# OTimCon_Station.net
KiCad netlist of a schematic drawn in Altium Designer
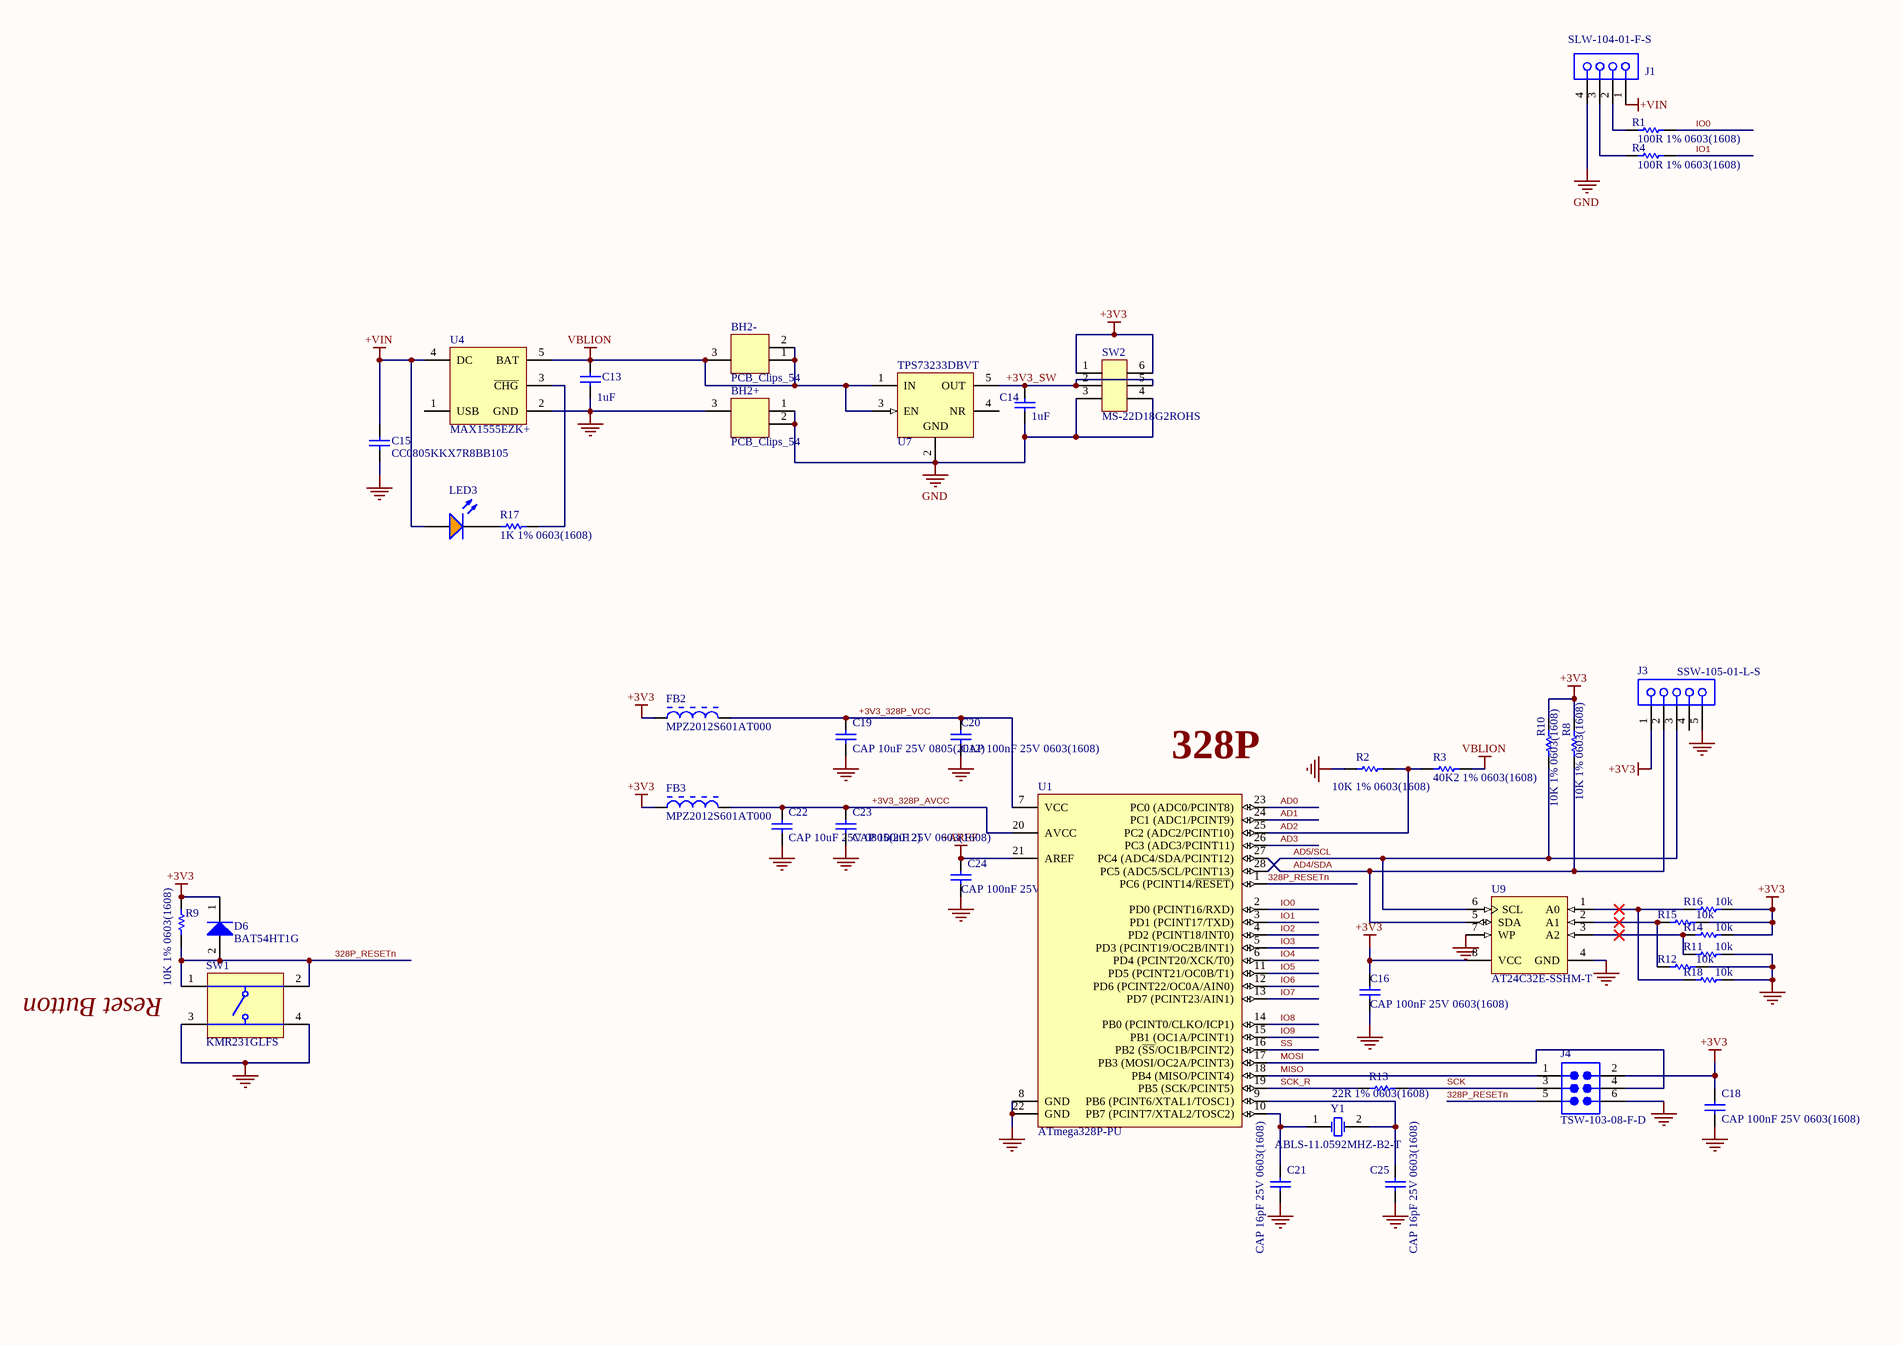
[diagram p0: OTimCon_Station.SchDoc, left]
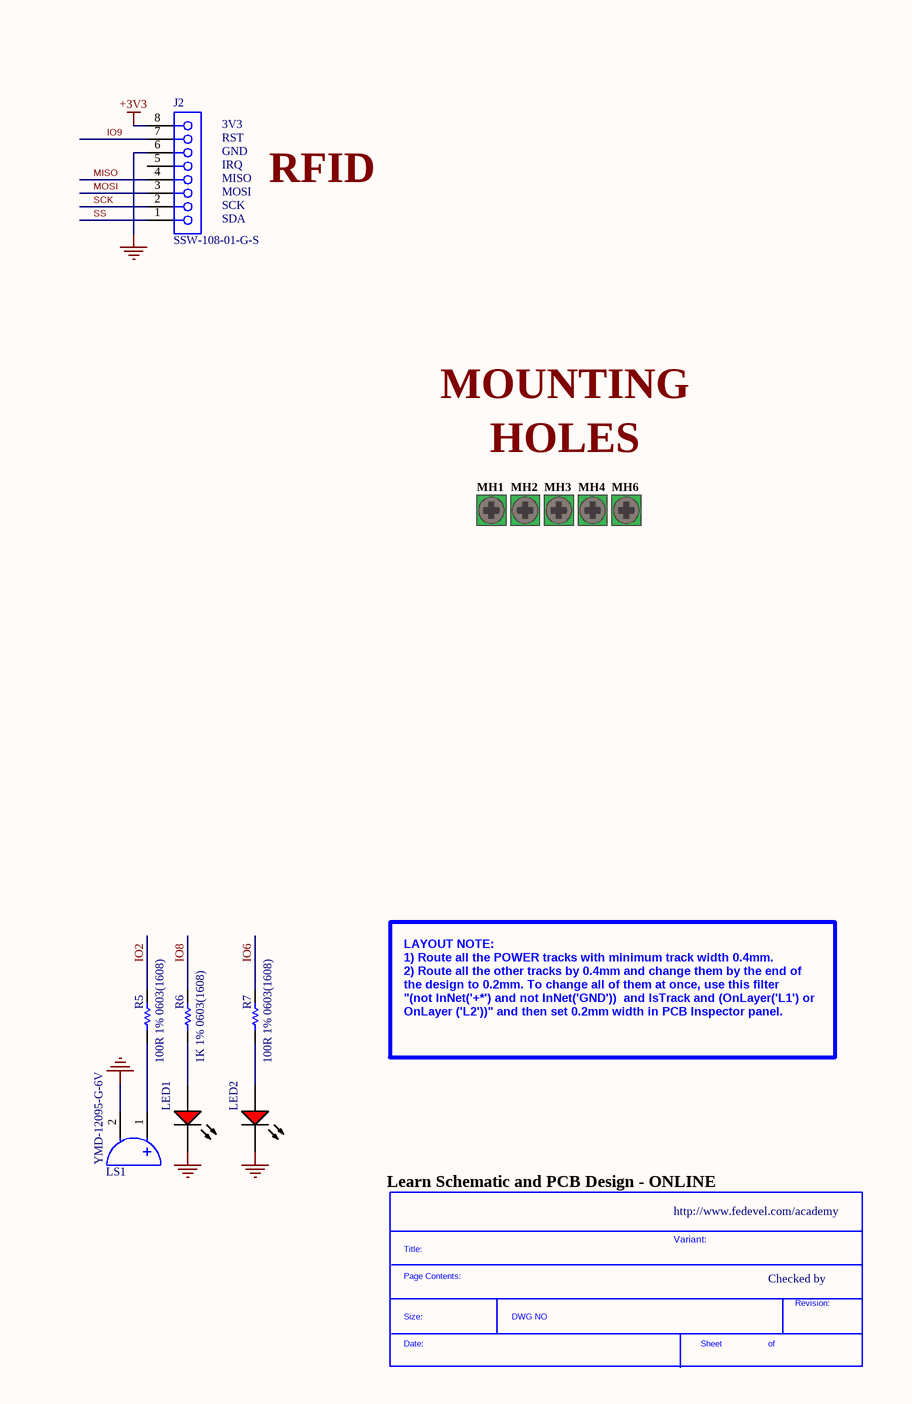
[diagram p1: OTimCon_Station.SchDoc, right]

(export (version "E")
  (design (tool "Eeschema 10.0.6"))
  (components
    (comp (ref "*") (value "SDTitleBlock") (libsource (lib "*") (part "SDTitleBlock")))
    (comp (ref "BH2+")
      (value "PCB_Clips_54")
      (footprint "KEYSTONE-CLIPS_54-3_V")
      (description "PC Battery Clip, Catalog No.54, Spring Steel, Body 18.102 x 13.004 mm, THM")
      (fields (field (name "MANUFACTURER") "Keystone"))
      (libsource (lib "Altium Content Vault") (part "KEYSTONE-CLIPS_54-3"))
    )
    (comp (ref "BH2-")
      (value "PCB_Clips_54")
      (footprint "KEYSTONE-CLIPS_54-3_V")
      (description "PC Battery Clip, Catalog No.54, Spring Steel, Body 18.102 x 13.004 mm, THM")
      (fields (field (name "MANUFACTURER") "Keystone"))
      (libsource (lib "") (part "KEYSTONE-CLIPS_54-3_1"))
    )
    (comp (ref "C13")
      (value "CC0805KKX7R8BB105")
      (footprint "CAPC2013X145X50ML20T25")
      (description "Chip Capacitor, 1 uF, 25 V, 10%, -55 to 125 degC, 0805 (2012 Metric), RoHS, Tape and Reel")
      (fields
        (field (name "CAPACITANCE") "1uF")
        (field (name "MANUFACTURER") "Yageo")
        (field (name "TOLERANCE") "10%")
      )
      (libsource (lib "Altium Content Vault") (part "CAP-NP-2"))
    )
    (comp (ref "C14")
      (value "CC0805KKX7R8BB105")
      (footprint "CAPC2013X145X50ML20T25")
      (description "Chip Capacitor, 1 uF, 25 V, 10%, -55 to 125 degC, 0805 (2012 Metric), RoHS, Tape and Reel")
      (fields
        (field (name "CAPACITANCE") "1uF")
        (field (name "MANUFACTURER") "Yageo")
        (field (name "TOLERANCE") "10%")
      )
      (libsource (lib "Altium Content Vault") (part "CAP-NP-2"))
    )
    (comp (ref "C15")
      (value "CC0805KKX7R8BB105")
      (footprint "CAPC2013X145X50ML20T25")
      (description "Chip Capacitor, 1 uF, 25 V, 10%, -55 to 125 degC, 0805 (2012 Metric), RoHS, Tape and Reel")
      (fields (field (name "MANUFACTURER") "Yageo") (field (name "TOLERANCE") "10%"))
      (libsource (lib "Altium Content Vault") (part "CAP-NP-2"))
    )
    (comp (ref "C16")
      (value "CAP 100nF 25V 0603(1608)")
      (footprint "CAPC0603(1608)100_M")
      (description "CAP 100nF 25V ±10% 0603 (1608 Metric) Thickness 1mm SMD")
      (fields (field (name "TOLERANCE") "Â±10%"))
      (libsource (lib "Altium Content Vault") (part "CAP"))
    )
    (comp (ref "C18")
      (value "CAP 100nF 25V 0603(1608)")
      (footprint "CAPC0603(1608)100_M")
      (description "CAP 100nF 25V ±10% 0603 (1608 Metric) Thickness 1mm SMD")
      (fields (field (name "TOLERANCE") "Â±10%"))
      (libsource (lib "Altium Content Vault") (part "CAP"))
    )
    (comp (ref "C19")
      (value "CAP 10uF 25V 0805(2012)")
      (footprint "CAPC0805(2012)145_N")
      (description "CAP 10uF 25V ±10% 0805 (2012 Metric) Thickness 1.45mm SMD")
      (fields (field (name "TOLERANCE") "Â±10%"))
      (libsource (lib "Altium Content Vault") (part "CAP"))
    )
    (comp (ref "C20")
      (value "CAP 100nF 25V 0603(1608)")
      (footprint "CAPC0603(1608)100_M")
      (description "CAP 100nF 25V ±10% 0603 (1608 Metric) Thickness 1mm SMD")
      (fields (field (name "TOLERANCE") "Â±10%"))
      (libsource (lib "Altium Content Vault") (part "CAP"))
    )
    (comp (ref "C21")
      (value "CAP 16pF 25V 0603(1608)")
      (footprint "CAPC0603(1608)100_L")
      (description "CAP 16pF 25V ±10% 0603 (1608 Metric) Thickness 1mm SMD")
      (fields (field (name "TOLERANCE") "Â±10%"))
      (libsource (lib "Altium Content Vault") (part "CAP"))
    )
    (comp (ref "C22")
      (value "CAP 10uF 25V 0805(2012)")
      (footprint "CAPC0805(2012)145_N")
      (description "CAP 10uF 25V ±10% 0805 (2012 Metric) Thickness 1.45mm SMD")
      (fields (field (name "TOLERANCE") "Â±10%"))
      (libsource (lib "Altium Content Vault") (part "CAP"))
    )
    (comp (ref "C23")
      (value "CAP 100nF 25V 0603(1608)")
      (footprint "CAPC0603(1608)100_M")
      (description "CAP 100nF 25V ±10% 0603 (1608 Metric) Thickness 1mm SMD")
      (fields (field (name "TOLERANCE") "Â±10%"))
      (libsource (lib "Altium Content Vault") (part "CAP"))
    )
    (comp (ref "C24")
      (value "CAP 100nF 25V 0603(1608)")
      (footprint "CAPC0603(1608)100_M")
      (description "CAP 100nF 25V ±10% 0603 (1608 Metric) Thickness 1mm SMD")
      (fields (field (name "TOLERANCE") "Â±10%"))
      (libsource (lib "Altium Content Vault") (part "CAP"))
    )
    (comp (ref "C25")
      (value "CAP 16pF 25V 0603(1608)")
      (footprint "CAPC0603(1608)100_L")
      (description "CAP 16pF 25V ±10% 0603 (1608 Metric) Thickness 1mm SMD")
      (fields (field (name "TOLERANCE") "Â±10%"))
      (libsource (lib "Altium Content Vault") (part "CAP"))
    )
    (comp (ref "D6")
      (value "BAT54HT1G")
      (footprint "ONSC-SOD-323-2-477-02_V")
      (description "Schottky Barrier Diode, 2-Pin SOD-323, Pb-Free, Tape and Reel")
      (fields (field (name "MANUFACTURER") "On Semiconductor"))
      (libsource (lib "Altium Content Vault") (part "ONSC-D-K1A2-2"))
    )
    (comp (ref "FB2")
      (value "MPZ2012S601AT000")
      (footprint "TDK-MPZ2012_V")
      (description "Chip Bead, 0.1 Ohm, 2 A, -55 to 125 degC, 2-Pin SMD (0805), RoHS, Tape and Reel")
      (fields (field (name "PCN PART NUMBER") "MMZ,MPSSeriesOct/2014") (field (name "MANUFACTURER") "TDK"))
      (libsource (lib "Altium Content Vault") (part "BEAD-2"))
    )
    (comp (ref "FB3")
      (value "MPZ2012S601AT000")
      (footprint "TDK-MPZ2012_V")
      (description "Chip Bead, 0.1 Ohm, 2 A, -55 to 125 degC, 2-Pin SMD (0805), RoHS, Tape and Reel")
      (fields (field (name "PCN PART NUMBER") "MMZ,MPSSeriesOct/2014") (field (name "MANUFACTURER") "TDK"))
      (libsource (lib "Altium Content Vault") (part "BEAD-2"))
    )
    (comp (ref "J1")
      (value "SLW-104-01-F-S")
      (footprint "SMTC-SLW-104-01-X-S")
      (fields (field (name "MANUFACTURER") "Samtec"))
      (libsource (lib "Altium Content Vault") (part "SMTC-SLW-104-01-X-S"))
    )
    (comp (ref "J2")
      (value "SSW-108-01-G-S")
      (footprint "SMTC-SSW-108-01-G-S")
      (description "SOCKET, Through-hole, Vertical, -55 to 125 degC, 2.54 mm Pitch, 8-Pin Female, RoHS")
      (fields (field (name "MANUFACTURER") "Samtec"))
      (libsource (lib "Altium Content Vault") (part "SMTC-SSW-108-01-G-S"))
    )
    (comp (ref "J3")
      (value "SSW-105-01-L-S")
      (footprint "SMTC-SSW-105-01-X-S")
      (description "SQ Post Socket, Through-hole, Vertical, -55 to 125 degC, 2.54mm Pitch, 5-Pin, Female, RoHS")
      (fields (field (name "MANUFACTURER") "Samtec"))
      (libsource (lib "Altium Content Vault") (part "SMTC-SSW-105-X-X-S"))
    )
    (comp (ref "J4")
      (value "TSW-103-08-F-D")
      (footprint "SMTC-TSW-103-08-X-D")
      (description "0.025\" SQ Post Header, Through-hole, Vertical, -55 to 125 degC, 2.54 mm Pitch, 6-Pin, Male, RoHS")
      (fields (field (name "MANUFACTURER") "Samtec"))
      (libsource (lib "Altium Content Vault") (part "SMTC-TSW-103-08-X-D"))
    )
    (comp (ref "LED1")
      (value "C503B-RAN-CY0B0AA2")
      (footprint "CREE-C503B-RAN")
      (description "Cree(R) 5-mm Red Round LED, 2.1 V, -40 to 100 degC, 2-Pin THD, RoHS, Ammo")
      (fields (field (name "MANUFACTURER") "Cree"))
      (libsource (lib "Altium Content Vault") (part "LED-RED-AK-2"))
    )
    (comp (ref "LED2")
      (value "C503B-RAN-CY0B0AA2")
      (footprint "CREE-C503B-RAN")
      (description "Cree(R) 5-mm Red Round LED, 2.1 V, -40 to 100 degC, 2-Pin THD, RoHS, Ammo")
      (fields (field (name "MANUFACTURER") "Cree"))
      (libsource (lib "Altium Content Vault") (part "LED-RED-AK-2"))
    )
    (comp (ref "LED3")
      (value "LTST-C190KFKT")
      (footprint "LTST-C190KFKT_V")
      (description "LED Uni-Color Orange, 75 mW, 30 mA, -35 to 85 degC, 2-Pin SMD, RoHS, Tape and Reel")
      (fields (field (name "TOLERANCE") "1%"))
      (libsource (lib "Altium Content Vault") (part "LED-ORANGE-AK-2"))
    )
    (comp (ref "LS1")
      (value "YMD-12095-G-6V")
      (footprint "HKDZ-YMD-12095-G-2_V")
      (description "Electromagnetic Active Buzzer, 6 V, 32 mA, -20 to 45 degC, 2-Pin THD, RoHS")
      (fields (field (name "MANUFACTURER") "Huakai Electronic"))
      (libsource (lib "Altium Content Vault") (part "HKDZ-YMD-12095-G-2"))
    )
    (comp (ref "MH1")
      (value "Mounting Hole (Screw)")
      (footprint "Mounting-Hole-Altium")
      (description "Mounting Hole, M3 Screw")
      (libsource (lib "Mounting-Hole-Screw") (part "Mounting-Hole-Screw"))
    )
    (comp (ref "MH2")
      (value "Mounting Hole (Screw)")
      (footprint "Mounting-Hole-Altium")
      (description "Mounting Hole, M3 Screw")
      (libsource (lib "Mounting-Hole-Screw") (part "Mounting-Hole-Screw"))
    )
    (comp (ref "MH3")
      (value "Mounting Hole (Screw)")
      (footprint "Mounting-Hole-Altium")
      (description "Mounting Hole, M3 Screw")
      (libsource (lib "Mounting-Hole-Screw") (part "Mounting-Hole-Screw"))
    )
    (comp (ref "MH4")
      (value "Mounting Hole (Screw)")
      (footprint "Mounting-Hole-Altium")
      (description "Mounting Hole, M3 Screw")
      (libsource (lib "Mounting-Hole-Screw") (part "Mounting-Hole-Screw"))
    )
    (comp (ref "MH6")
      (value "Mounting Hole (Screw)")
      (footprint "Mounting-Hole-Altium")
      (description "Mounting Hole, M3 Screw")
      (libsource (lib "Mounting-Hole-Screw") (part "Mounting-Hole-Screw"))
    )
    (comp (ref "R1")
      (value "100R 1% 0603(1608)")
      (footprint "RESC0603(1608)_M")
      (description "100R 0.1W 1% 0603 (1608 Metric)  SMD")
      (fields (field (name "TOLERANCE") "1 %") (field (name "POWER") "0.1 W"))
      (libsource (lib "Altium Content Vault") (part "RES"))
    )
    (comp (ref "R2")
      (value "10K 1% 0603(1608)")
      (footprint "RESC0603(1608)_N")
      (description "10K 0.1W 1% 0603 (1608 Metric)  SMD")
      (fields (field (name "POWER") "0.1 W") (field (name "TOLERANCE") "1 %"))
      (libsource (lib "Altium Content Vault") (part "RES"))
    )
    (comp (ref "R3")
      (value "40K2 1% 0603(1608)")
      (footprint "RESC0603(1608)_M")
      (description "40K2 0.1W 1% 0603 (1608 Metric)  SMD")
      (fields (field (name "TOLERANCE") "1 %") (field (name "POWER") "0.1 W"))
      (libsource (lib "Altium Content Vault") (part "RES"))
    )
    (comp (ref "R4")
      (value "100R 1% 0603(1608)")
      (footprint "RESC0603(1608)_M")
      (description "100R 0.1W 1% 0603 (1608 Metric)  SMD")
      (fields (field (name "TOLERANCE") "1 %") (field (name "POWER") "0.1 W"))
      (libsource (lib "Altium Content Vault") (part "RES"))
    )
    (comp (ref "R5")
      (value "100R 1% 0603(1608)")
      (footprint "RESC0603(1608)_M")
      (description "100R 0.1W 1% 0603 (1608 Metric)  SMD")
      (fields (field (name "TOLERANCE") "1 %") (field (name "POWER") "0.1 W"))
      (libsource (lib "Altium Content Vault") (part "RES"))
    )
    (comp (ref "R6")
      (value "1K 1% 0603(1608)")
      (footprint "RESC0603(1608)_M")
      (description "1K 0.1W 1% 0603 (1608 Metric)  SMD")
      (fields (field (name "TOLERANCE") "1 %") (field (name "POWER") "0.1 W"))
      (libsource (lib "Altium Content Vault") (part "RES"))
    )
    (comp (ref "R7")
      (value "100R 1% 0603(1608)")
      (footprint "RESC0603(1608)_M")
      (description "100R 0.1W 1% 0603 (1608 Metric)  SMD")
      (fields (field (name "TOLERANCE") "1 %") (field (name "POWER") "0.1 W"))
      (libsource (lib "Altium Content Vault") (part "RES"))
    )
    (comp (ref "R8")
      (value "10K 1% 0603(1608)")
      (footprint "RESC0603(1608)_N")
      (description "10K 0.1W 1% 0603 (1608 Metric)  SMD")
      (fields (field (name "POWER") "0.1 W") (field (name "TOLERANCE") "1 %"))
      (libsource (lib "Altium Content Vault") (part "RES"))
    )
    (comp (ref "R9")
      (value "10K 1% 0603(1608)")
      (footprint "RESC0603(1608)_N")
      (description "10K 0.1W 1% 0603 (1608 Metric)  SMD")
      (fields (field (name "POWER") "0.1 W") (field (name "TOLERANCE") "1 %"))
      (libsource (lib "Altium Content Vault") (part "RES"))
    )
    (comp (ref "R10")
      (value "10K 1% 0603(1608)")
      (footprint "RESC0603(1608)_N")
      (description "10K 0.1W 1% 0603 (1608 Metric)  SMD")
      (fields (field (name "POWER") "0.1 W") (field (name "TOLERANCE") "1 %"))
      (libsource (lib "Altium Content Vault") (part "RES"))
    )
    (comp (ref "R11")
      (value "10k")
      (footprint "RESC0603(1608)_N")
      (description "10K 0.1W 1% 0603 (1608 Metric)  SMD")
      (fields (field (name "POWER") "0.1 W") (field (name "TOLERANCE") "1 %"))
      (libsource (lib "Altium Content Vault") (part "RES"))
    )
    (comp (ref "R12")
      (value "10k")
      (footprint "RESC0603(1608)_N")
      (description "10K 0.1W 1% 0603 (1608 Metric)  SMD")
      (fields (field (name "POWER") "0.1 W") (field (name "TOLERANCE") "1 %"))
      (libsource (lib "Altium Content Vault") (part "RES"))
    )
    (comp (ref "R13")
      (value "22R 1% 0603(1608)")
      (footprint "RESC0603(1608)_M")
      (description "22R 0.1W 1% 0603 (1608 Metric)  SMD")
      (fields (field (name "POWER") "0.1 W") (field (name "TOLERANCE") "1 %"))
      (libsource (lib "Altium Content Vault") (part "RES"))
    )
    (comp (ref "R14")
      (value "10k")
      (footprint "RESC0603(1608)_N")
      (description "10K 0.1W 1% 0603 (1608 Metric)  SMD")
      (fields (field (name "POWER") "0.1 W") (field (name "TOLERANCE") "1 %"))
      (libsource (lib "Altium Content Vault") (part "RES"))
    )
    (comp (ref "R15")
      (value "10k")
      (footprint "RESC0603(1608)_N")
      (description "10K 0.1W 1% 0603 (1608 Metric)  SMD")
      (fields (field (name "POWER") "0.1 W") (field (name "TOLERANCE") "1 %"))
      (libsource (lib "Altium Content Vault") (part "RES"))
    )
    (comp (ref "R16")
      (value "10k")
      (footprint "RESC0603(1608)_N")
      (description "10K 0.1W 1% 0603 (1608 Metric)  SMD")
      (fields (field (name "POWER") "0.1 W") (field (name "TOLERANCE") "1 %"))
      (libsource (lib "Altium Content Vault") (part "RES"))
    )
    (comp (ref "R17")
      (value "1K 1% 0603(1608)")
      (footprint "RESC0603(1608)_M")
      (description "1K 0.1W 1% 0603 (1608 Metric)  SMD")
      (fields (field (name "TOLERANCE") "1 %") (field (name "POWER") "0.1 W"))
      (libsource (lib "Altium Content Vault") (part "RES"))
    )
    (comp (ref "R18")
      (value "10k")
      (footprint "RESC0603(1608)_N")
      (description "10K 0.1W 1% 0603 (1608 Metric)  SMD")
      (fields (field (name "POWER") "0.1 W") (field (name "TOLERANCE") "1 %"))
      (libsource (lib "Altium Content Vault") (part "RES"))
    )
    (comp (ref "SW1")
      (value "KMR231GLFS")
      (footprint "CKCP-KMR231GLFS")
      (description "Switch Tactile, SPST, 50 mA, 32 V, -40 to 85 degC, 4-Pin SMD, RoHS, Tape and Reel")
      (fields (field (name "MANUFACTURER") "C&K Components"))
      (libsource (lib "Altium Content Vault") (part "SW-SPST-4_A"))
    )
    (comp (ref "SW2")
      (value "MS-22D18G2ROHS")
      (footprint "DYL-MS22D18G2ROHS-6_V")
      (description "Slide Switch, 30 V, 0.3 A, -20 to 80 degC, 6-Pin THD, RoHS")
      (fields (field (name "MANUFACTURER") "Deyilong"))
      (libsource (lib "Altium Content Vault") (part "DYL-MS22D18G2ROHS-6"))
    )
    (comp (ref "U1")
      (value "ATmega328P-PU")
      (footprint "28P3")
      (libsource (lib "Altium Content Vault") (part "MC-8B-ATM48-IL28"))
    )
    (comp (ref "U4")
      (value "MAX1555EZK+")
      (footprint "MAXM-Z5+1_M")
      (fields (field (name "MANUFACTURER") "Maxim"))
      (libsource (lib "Altium Content Vault") (part "MAXM-MAX1555-Z5+1"))
    )
    (comp (ref "U7")
      (value "TPS73233DBVT")
      (footprint "DBV0005A_N")
      (fields (field (name "MANUFACTURER") "Texas Instruments"))
      (libsource (lib "Altium Content Vault") (part "TI-TPS79NXX-YYSOT5"))
    )
    (comp (ref "U9")
      (value "AT24C32E-SSHM-T")
      (footprint "ATML-8S1_A_L")
      (fields (field (name "GENERIC PART NUMBER") "AT24C32E"))
      (libsource (lib "Altium Content Vault") (part "ATMEL-AT24C32E-SSHM-T-8"))
    )
    (comp (ref "Y1")
      (value "ABLS-11.0592MHZ-B2-T")
      (footprint "ABRA-ABLS-11.0592MHZ-B2-T_V")
      (description "HC / 49 US (AT49) Low Profile Crystal, 11.0592 MHz, 0 to 70 degC, 2-Pin SMD, RoHS, Tape and Reel")
      (fields (field (name "TOLERANCE") "20PPM") (field (name "MANUFACTURER") "ABRACON"))
      (libsource (lib "Altium Content Vault") (part "XTAL_1-2-2"))
    )
  )
  (nets
    (net (code "1") (name "+3V3") (class "Default")
      (node (ref "C16") (pin "2") (pinfunction "2_2") (pintype "passive"))
      (node (ref "C18") (pin "2") (pinfunction "2_2") (pintype "passive"))
      (node (ref "D6") (pin "1") (pinfunction "K_1") (pintype "passive"))
      (node (ref "FB2") (pin "1") (pinfunction "1_1") (pintype "passive"))
      (node (ref "FB3") (pin "1") (pinfunction "1_1") (pintype "passive"))
      (node (ref "J2") (pin "8") (pinfunction "8_8") (pintype "passive"))
      (node (ref "J3") (pin "1") (pinfunction "1_1") (pintype "passive"))
      (node (ref "J4") (pin "2") (pinfunction "2_2") (pintype "passive"))
      (node (ref "R10") (pin "1") (pinfunction "1_1") (pintype "passive"))
      (node (ref "R14") (pin "2") (pinfunction "2_2") (pintype "passive"))
      (node (ref "R15") (pin "1") (pinfunction "1_1") (pintype "passive"))
      (node (ref "R16") (pin "2") (pinfunction "2_2") (pintype "passive"))
      (node (ref "R8") (pin "1") (pinfunction "1_1") (pintype "passive"))
      (node (ref "R9") (pin "1") (pinfunction "1_1") (pintype "passive"))
      (node (ref "SW2") (pin "1") (pinfunction "1_1") (pintype "passive"))
      (node (ref "SW2") (pin "6") (pinfunction "6_6") (pintype "passive"))
      (node (ref "U9") (pin "8") (pinfunction "VCC_8") (pintype "power_in"))
    )
    (net (code "2") (name "+AREF") (class "Default")
      (node (ref "C24") (pin "2") (pinfunction "2_2") (pintype "passive"))
      (node (ref "U1") (pin "21") (pinfunction "AREF_21") (pintype "power_in"))
    )
    (net (code "3") (name "+VIN") (class "Default")
      (node (ref "C15") (pin "1") (pinfunction "1_1") (pintype "passive"))
      (node (ref "J1") (pin "1") (pinfunction "1_1") (pintype "passive"))
      (node (ref "LED3") (pin "1") (pinfunction "A_1") (pintype "passive"))
      (node (ref "U4") (pin "4") (pinfunction "DC_4") (pintype "power_in"))
    )
    (net (code "4") (name "/+3V3_328P_AVCC") (class "Default")
      (node (ref "C22") (pin "2") (pinfunction "2_2") (pintype "passive"))
      (node (ref "C23") (pin "2") (pinfunction "2_2") (pintype "passive"))
      (node (ref "FB3") (pin "2") (pinfunction "2_2") (pintype "passive"))
      (node (ref "U1") (pin "20") (pinfunction "AVCC_20") (pintype "power_in"))
    )
    (net (code "5") (name "/+3V3_328P_VCC") (class "Default")
      (node (ref "C19") (pin "2") (pinfunction "2_2") (pintype "passive"))
      (node (ref "C20") (pin "2") (pinfunction "2_2") (pintype "passive"))
      (node (ref "FB2") (pin "2") (pinfunction "2_2") (pintype "passive"))
      (node (ref "U1") (pin "7") (pinfunction "VCC_7") (pintype "power_in"))
    )
    (net (code "6") (name "/+3V3_SW") (class "Default")
      (node (ref "C14") (pin "1") (pinfunction "1_1") (pintype "passive"))
      (node (ref "SW2") (pin "2") (pinfunction "2_2") (pintype "passive"))
      (node (ref "SW2") (pin "5") (pinfunction "5_5") (pintype "passive"))
      (node (ref "U7") (pin "5") (pinfunction "OUT_5") (pintype "power_in"))
    )
    (net (code "7") (name "/328P_RESETn") (class "Default")
      (node (ref "D6") (pin "2") (pinfunction "A_2") (pintype "passive"))
      (node (ref "J4") (pin "5") (pinfunction "5_5") (pintype "passive"))
      (node (ref "R9") (pin "2") (pinfunction "2_2") (pintype "passive"))
      (node (ref "SW1") (pin "1") (pinfunction "1_1") (pintype "passive"))
      (node (ref "SW1") (pin "2") (pinfunction "2_2") (pintype "passive"))
      (node (ref "U1") (pin "1") (pinfunction "PC6_(PCINT14/~{RESET})_1") (pintype "bidirectional"))
    )
    (net (code "8") (name "/AD0") (class "Default")
      (node (ref "U1") (pin "23") (pinfunction "PC0_(ADC0/PCINT8)_23") (pintype "bidirectional"))
    )
    (net (code "9") (name "/AD1") (class "Default")
      (node (ref "U1") (pin "24") (pinfunction "PC1_(ADC1/PCINT9)_24") (pintype "bidirectional"))
    )
    (net (code "10") (name "/AD2") (class "Default")
      (node (ref "R2") (pin "2") (pinfunction "2_2") (pintype "passive"))
      (node (ref "R3") (pin "1") (pinfunction "1_1") (pintype "passive"))
      (node (ref "U1") (pin "25") (pinfunction "PC2_(ADC2/PCINT10)_25") (pintype "bidirectional"))
    )
    (net (code "11") (name "/AD3") (class "Default")
      (node (ref "U1") (pin "26") (pinfunction "PC3_(ADC3/PCINT11)_26") (pintype "bidirectional"))
    )
    (net (code "12") (name "/AD4{slash}SDA") (class "Default")
      (node (ref "J3") (pin "2") (pinfunction "2_2") (pintype "passive"))
      (node (ref "R8") (pin "2") (pinfunction "2_2") (pintype "passive"))
      (node (ref "U1") (pin "27") (pinfunction "PC4_(ADC4/SDA/PCINT12)_27") (pintype "bidirectional"))
      (node (ref "U9") (pin "5") (pinfunction "SDA_5") (pintype "bidirectional"))
    )
    (net (code "13") (name "/AD5{slash}SCL") (class "Default")
      (node (ref "J3") (pin "3") (pinfunction "3_3") (pintype "passive"))
      (node (ref "R10") (pin "2") (pinfunction "2_2") (pintype "passive"))
      (node (ref "U1") (pin "28") (pinfunction "PC5_(ADC5/SCL/PCINT13)_28") (pintype "bidirectional"))
      (node (ref "U9") (pin "6") (pinfunction "SCL_6") (pintype "input"))
    )
    (net (code "14") (name "/IO0") (class "Default")
      (node (ref "R1") (pin "2") (pinfunction "2_2") (pintype "passive"))
      (node (ref "U1") (pin "2") (pinfunction "PD0_(PCINT16/RXD)_2") (pintype "bidirectional"))
    )
    (net (code "15") (name "/IO1") (class "Default")
      (node (ref "R4") (pin "2") (pinfunction "2_2") (pintype "passive"))
      (node (ref "U1") (pin "3") (pinfunction "PD1_(PCINT17/TXD)_3") (pintype "bidirectional"))
    )
    (net (code "16") (name "/IO2") (class "Default")
      (node (ref "R5") (pin "2") (pinfunction "2_2") (pintype "passive"))
      (node (ref "U1") (pin "4") (pinfunction "PD2_(PCINT18/INT0)_4") (pintype "bidirectional"))
    )
    (net (code "17") (name "/IO3") (class "Default")
      (node (ref "U1") (pin "5") (pinfunction "PD3_(PCINT19/OC2B/INT1)_5") (pintype "bidirectional"))
    )
    (net (code "18") (name "/IO4") (class "Default")
      (node (ref "U1") (pin "6") (pinfunction "PD4_(PCINT20/XCK/T0)_6") (pintype "bidirectional"))
    )
    (net (code "19") (name "/IO5") (class "Default")
      (node (ref "U1") (pin "11") (pinfunction "PD5_(PCINT21/OC0B/T1)_11") (pintype "bidirectional"))
    )
    (net (code "20") (name "/IO6") (class "Default")
      (node (ref "R7") (pin "2") (pinfunction "2_2") (pintype "passive"))
      (node (ref "U1") (pin "12") (pinfunction "PD6_(PCINT22/OC0A/AIN0)_12") (pintype "bidirectional"))
    )
    (net (code "21") (name "/IO7") (class "Default")
      (node (ref "U1") (pin "13") (pinfunction "PD7_(PCINT23/AIN1)_13") (pintype "bidirectional"))
    )
    (net (code "22") (name "/IO8") (class "Default")
      (node (ref "R6") (pin "1") (pinfunction "1_1") (pintype "passive"))
      (node (ref "U1") (pin "14") (pinfunction "PB0_(PCINT0/CLKO/ICP1)_14") (pintype "bidirectional"))
    )
    (net (code "23") (name "/IO9") (class "Default")
      (node (ref "J2") (pin "7") (pinfunction "7_7") (pintype "passive"))
      (node (ref "U1") (pin "15") (pinfunction "PB1_(OC1A/PCINT1)_15") (pintype "bidirectional"))
    )
    (net (code "24") (name "/MISO") (class "Default")
      (node (ref "J2") (pin "4") (pinfunction "4_4") (pintype "passive"))
      (node (ref "J4") (pin "1") (pinfunction "1_1") (pintype "passive"))
      (node (ref "U1") (pin "18") (pinfunction "PB4_(MISO/PCINT4)_18") (pintype "bidirectional"))
    )
    (net (code "25") (name "/MOSI") (class "Default")
      (node (ref "J2") (pin "3") (pinfunction "3_3") (pintype "passive"))
      (node (ref "J4") (pin "4") (pinfunction "4_4") (pintype "passive"))
      (node (ref "U1") (pin "17") (pinfunction "PB3_(MOSI/OC2A/PCINT3)_17") (pintype "bidirectional"))
    )
    (net (code "26") (name "/SCK") (class "Default")
      (node (ref "J2") (pin "2") (pinfunction "2_2") (pintype "passive"))
      (node (ref "J4") (pin "3") (pinfunction "3_3") (pintype "passive"))
      (node (ref "R13") (pin "2") (pinfunction "2_2") (pintype "passive"))
    )
    (net (code "27") (name "/SCK_R") (class "Default")
      (node (ref "R13") (pin "1") (pinfunction "1_1") (pintype "passive"))
      (node (ref "U1") (pin "19") (pinfunction "PB5_(SCK/PCINT5)_19") (pintype "bidirectional"))
    )
    (net (code "28") (name "/SS") (class "Default")
      (node (ref "J2") (pin "1") (pinfunction "1_1") (pintype "passive"))
      (node (ref "U1") (pin "16") (pinfunction "PB2_(~{SS}/OC1B/PCINT2)_16") (pintype "bidirectional"))
    )
    (net (code "29") (name "GND") (class "Default")
      (node (ref "BH2+") (pin "1") (pinfunction "1_1") (pintype "power_in"))
      (node (ref "BH2+") (pin "2") (pinfunction "2_2") (pintype "passive"))
      (node (ref "BH2+") (pin "3") (pinfunction "3_3") (pintype "passive"))
      (node (ref "C13") (pin "2") (pinfunction "2_2") (pintype "passive"))
      (node (ref "C14") (pin "2") (pinfunction "2_2") (pintype "passive"))
      (node (ref "C15") (pin "2") (pinfunction "2_2") (pintype "passive"))
      (node (ref "C16") (pin "1") (pinfunction "1_1") (pintype "passive"))
      (node (ref "C18") (pin "1") (pinfunction "1_1") (pintype "passive"))
      (node (ref "C19") (pin "1") (pinfunction "1_1") (pintype "passive"))
      (node (ref "C20") (pin "1") (pinfunction "1_1") (pintype "passive"))
      (node (ref "C21") (pin "1") (pinfunction "1_1") (pintype "passive"))
      (node (ref "C22") (pin "1") (pinfunction "1_1") (pintype "passive"))
      (node (ref "C23") (pin "1") (pinfunction "1_1") (pintype "passive"))
      (node (ref "C24") (pin "1") (pinfunction "1_1") (pintype "passive"))
      (node (ref "C25") (pin "1") (pinfunction "1_1") (pintype "passive"))
      (node (ref "J1") (pin "4") (pinfunction "4_4") (pintype "passive"))
      (node (ref "J2") (pin "6") (pinfunction "6_6") (pintype "passive"))
      (node (ref "J3") (pin "5") (pinfunction "5_5") (pintype "passive"))
      (node (ref "J4") (pin "6") (pinfunction "6_6") (pintype "passive"))
      (node (ref "LED1") (pin "2") (pinfunction "K_2") (pintype "passive"))
      (node (ref "LED2") (pin "2") (pinfunction "K_2") (pintype "passive"))
      (node (ref "LS1") (pin "2") (pinfunction "K_2") (pintype "passive"))
      (node (ref "R11") (pin "2") (pinfunction "2_2") (pintype "passive"))
      (node (ref "R12") (pin "1") (pinfunction "1_1") (pintype "passive"))
      (node (ref "R18") (pin "2") (pinfunction "2_2") (pintype "passive"))
      (node (ref "R2") (pin "1") (pinfunction "1_1") (pintype "passive"))
      (node (ref "SW1") (pin "3") (pinfunction "3_3") (pintype "passive"))
      (node (ref "SW1") (pin "4") (pinfunction "4_4") (pintype "passive"))
      (node (ref "SW2") (pin "3") (pinfunction "3_3") (pintype "passive"))
      (node (ref "SW2") (pin "4") (pinfunction "4_4") (pintype "passive"))
      (node (ref "U1") (pin "22") (pinfunction "GND_22") (pintype "power_in"))
      (node (ref "U1") (pin "8") (pinfunction "GND_8") (pintype "power_in"))
      (node (ref "U4") (pin "2") (pinfunction "GND_2") (pintype "power_in"))
      (node (ref "U7") (pin "2") (pinfunction "GND_2") (pintype "power_in"))
      (node (ref "U9") (pin "4") (pinfunction "GND_4") (pintype "power_in"))
      (node (ref "U9") (pin "7") (pinfunction "WP_7") (pintype "input"))
    )
    (net (code "30") (name "Net-(J1-Pad2)") (class "Default")
      (node (ref "J1") (pin "2") (pinfunction "2_2") (pintype "passive"))
      (node (ref "R1") (pin "1") (pinfunction "1_1") (pintype "passive"))
    )
    (net (code "31") (name "Net-(J1-Pad3)") (class "Default")
      (node (ref "J1") (pin "3") (pinfunction "3_3") (pintype "passive"))
      (node (ref "R4") (pin "1") (pinfunction "1_1") (pintype "passive"))
    )
    (net (code "32") (name "Net-(LED1-A)") (class "Default")
      (node (ref "LED1") (pin "1") (pinfunction "A_1") (pintype "passive"))
      (node (ref "R6") (pin "2") (pinfunction "2_2") (pintype "passive"))
    )
    (net (code "33") (name "Net-(LED2-A)") (class "Default")
      (node (ref "LED2") (pin "1") (pinfunction "A_1") (pintype "passive"))
      (node (ref "R7") (pin "1") (pinfunction "1_1") (pintype "passive"))
    )
    (net (code "34") (name "Net-(LED3-K)") (class "Default")
      (node (ref "LED3") (pin "2") (pinfunction "K_2") (pintype "passive"))
      (node (ref "R17") (pin "1") (pinfunction "1_1") (pintype "passive"))
    )
    (net (code "35") (name "Net-(LS1-A)") (class "Default")
      (node (ref "LS1") (pin "1") (pinfunction "A_1") (pintype "passive"))
      (node (ref "R5") (pin "1") (pinfunction "1_1") (pintype "passive"))
    )
    (net (code "36") (name "Net-(U1-PB6_(PCINT6{slash}XTAL1{slash}TOSC1))") (class "Default")
      (node (ref "C25") (pin "2") (pinfunction "2_2") (pintype "passive"))
      (node (ref "U1") (pin "9") (pinfunction "PB6_(PCINT6/XTAL1/TOSC1)_9") (pintype "bidirectional"))
      (node (ref "Y1") (pin "2") (pinfunction "X2_2") (pintype "passive"))
    )
    (net (code "37") (name "Net-(U1-PB7_(PCINT7{slash}XTAL2{slash}TOSC2))") (class "Default")
      (node (ref "C21") (pin "2") (pinfunction "2_2") (pintype "passive"))
      (node (ref "U1") (pin "10") (pinfunction "PB7_(PCINT7/XTAL2/TOSC2)_10") (pintype "bidirectional"))
      (node (ref "Y1") (pin "1") (pinfunction "X1_1") (pintype "passive"))
    )
    (net (code "38") (name "Net-(U4-~{CHG})") (class "Default")
      (node (ref "R17") (pin "2") (pinfunction "2_2") (pintype "passive"))
      (node (ref "U4") (pin "3") (pinfunction "~{CHG}_3") (pintype "tri_state"))
    )
    (net (code "39") (name "Net-(U9-A0)") (class "Default")
      (node (ref "R16") (pin "1") (pinfunction "1_1") (pintype "passive"))
      (node (ref "R18") (pin "1") (pinfunction "1_1") (pintype "passive"))
      (node (ref "U9") (pin "1") (pinfunction "A0_1") (pintype "input"))
    )
    (net (code "40") (name "Net-(U9-A1)") (class "Default")
      (node (ref "R12") (pin "2") (pinfunction "2_2") (pintype "passive"))
      (node (ref "R15") (pin "2") (pinfunction "2_2") (pintype "passive"))
      (node (ref "U9") (pin "2") (pinfunction "A1_2") (pintype "input"))
    )
    (net (code "41") (name "Net-(U9-A2)") (class "Default")
      (node (ref "R11") (pin "1") (pinfunction "1_1") (pintype "passive"))
      (node (ref "R14") (pin "1") (pinfunction "1_1") (pintype "passive"))
      (node (ref "U9") (pin "3") (pinfunction "A2_3") (pintype "input"))
    )
    (net (code "42") (name "VBLION") (class "Default")
      (node (ref "BH2-") (pin "1") (pinfunction "1_1") (pintype "power_in"))
      (node (ref "BH2-") (pin "2") (pinfunction "2_2") (pintype "passive"))
      (node (ref "BH2-") (pin "3") (pinfunction "3_3") (pintype "passive"))
      (node (ref "C13") (pin "1") (pinfunction "1_1") (pintype "passive"))
      (node (ref "R3") (pin "2") (pinfunction "2_2") (pintype "passive"))
      (node (ref "U4") (pin "5") (pinfunction "BAT_5") (pintype "power_in"))
      (node (ref "U7") (pin "1") (pinfunction "IN_1") (pintype "power_in"))
      (node (ref "U7") (pin "3") (pinfunction "EN_3") (pintype "input"))
    )
    (net (code "43") (name "unconnected-(J2-Pad5)") (class "Default")
      (node (ref "J2") (pin "5") (pinfunction "5_5") (pintype "passive"))
    )
    (net (code "44") (name "unconnected-(J3-Pad4)") (class "Default")
      (node (ref "J3") (pin "4") (pinfunction "4_4") (pintype "passive"))
    )
    (net (code "45") (name "unconnected-(MH1-Pad1)") (class "Default")
      (node (ref "MH1") (pin "1") (pinfunction "1_1") (pintype "passive"))
    )
    (net (code "46") (name "unconnected-(MH2-Pad1)") (class "Default")
      (node (ref "MH2") (pin "1") (pinfunction "1_1") (pintype "passive"))
    )
    (net (code "47") (name "unconnected-(MH3-Pad1)") (class "Default")
      (node (ref "MH3") (pin "1") (pinfunction "1_1") (pintype "passive"))
    )
    (net (code "48") (name "unconnected-(MH4-Pad1)") (class "Default")
      (node (ref "MH4") (pin "1") (pinfunction "1_1") (pintype "passive"))
    )
    (net (code "49") (name "unconnected-(MH6-Pad1)") (class "Default")
      (node (ref "MH6") (pin "1") (pinfunction "1_1") (pintype "passive"))
    )
    (net (code "50") (name "unconnected-(U4-USB-Pad1)") (class "Default")
      (node (ref "U4") (pin "1") (pinfunction "USB_1") (pintype "power_in"))
    )
    (net (code "51") (name "unconnected-(U7-NR-Pad4)") (class "Default")
      (node (ref "U7") (pin "4") (pinfunction "NR_4") (pintype "passive"))
    )
  )
)
